# JasminUSBASP.net
KiCad netlist of a schematic drawn in EAGLE
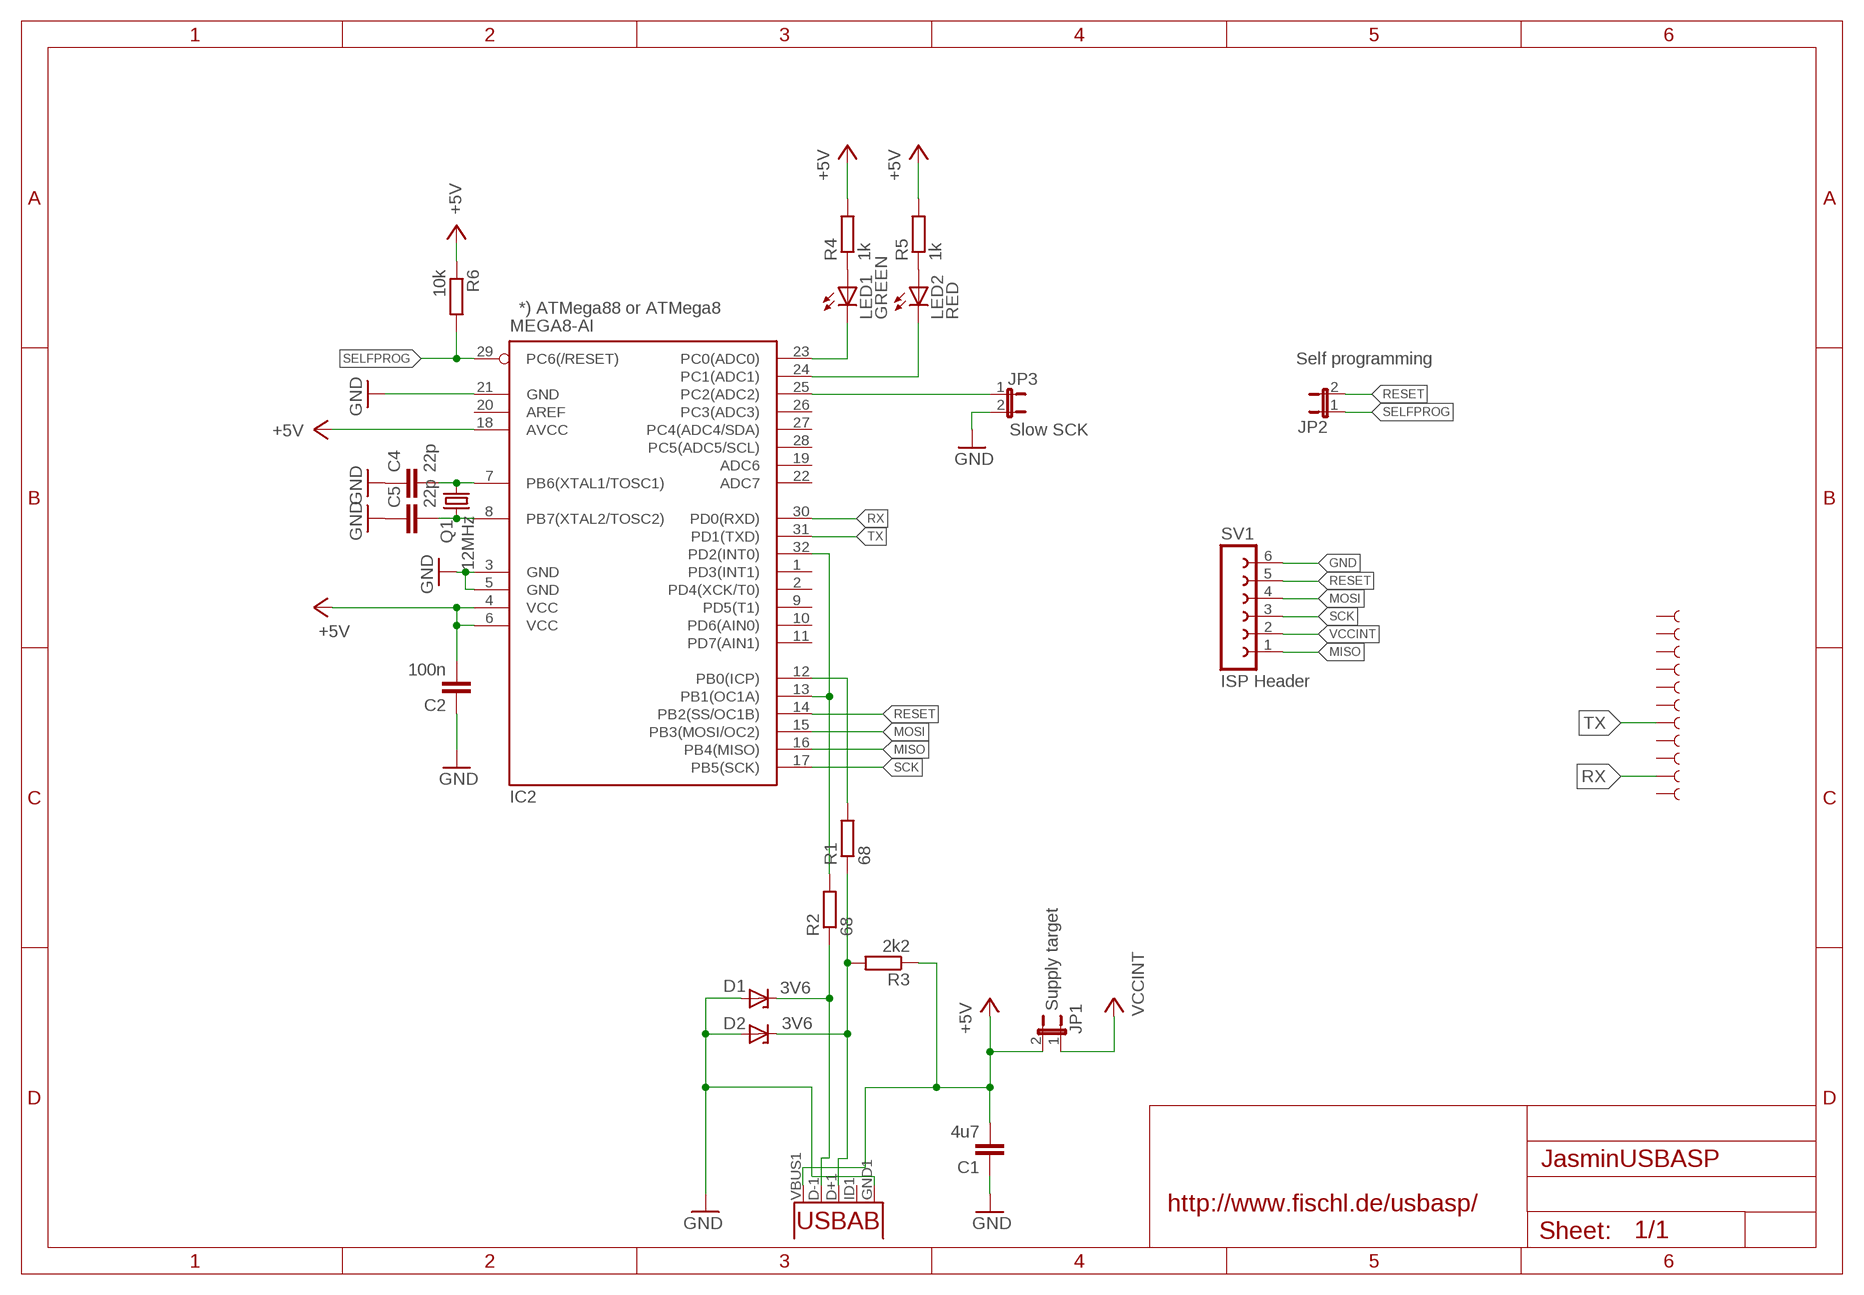
[diagram p0: schematic, sheet 1]

(export (version "E")
  (design (tool "Eeschema 10.0.6"))
  (components
    (comp (ref "A2/16")
      (value "SEWTAP9")
      (footprint "eagle-import:PETAL-LONG-1-2SIDE")
      (libsource (lib "eagle-import") (part "SEWTAP9"))
    )
    (comp (ref "A3/17")
      (value "SEWTAP9")
      (footprint "eagle-import:PETAL-LONG-1-2SIDE")
      (libsource (lib "eagle-import") (part "SEWTAP9"))
    )
    (comp (ref "A4/18")
      (value "SEWTAP9")
      (footprint "eagle-import:PETAL-LONG-1-2SIDE")
      (libsource (lib "eagle-import") (part "SEWTAP9"))
    )
    (comp (ref "A5/19")
      (value "SEWTAP9")
      (footprint "eagle-import:PETAL-LONG-1-2SIDE")
      (libsource (lib "eagle-import") (part "SEWTAP9"))
    )
    (comp (ref "C1")
      (value "4u7")
      (footprint "eagle-import:C1206")
      (libsource (lib "eagle-import") (part "C-EUC1206"))
    )
    (comp (ref "C2")
      (value "100n")
      (footprint "eagle-import:C1206")
      (libsource (lib "eagle-import") (part "C-EUC1206"))
    )
    (comp (ref "C4")
      (value "22p")
      (footprint "eagle-import:C1206")
      (libsource (lib "eagle-import") (part "C-EUC1206"))
    )
    (comp (ref "C5")
      (value "22p")
      (footprint "eagle-import:C1206")
      (libsource (lib "eagle-import") (part "C-EUC1206"))
    )
    (comp (ref "D1")
      (value "3V6")
      (footprint "eagle-import:DO34Z7")
      (libsource (lib "eagle-import") (part "ZENER-DIODEDO34-7"))
    )
    (comp (ref "D2")
      (value "3V6")
      (footprint "eagle-import:DO34Z7")
      (libsource (lib "eagle-import") (part "ZENER-DIODEDO34-7"))
    )
    (comp (ref "IC2")
      (value "MEGA8-AI")
      (footprint "eagle-import:TQFP32-08")
      (fields (field (name "MPN") "ATMEGA8-16AU"))
      (libsource (lib "eagle-import") (part "MEGA8-AI"))
    )
    (comp (ref "JP1")
      (value "Supply target")
      (footprint "eagle-import:JP1")
      (libsource (lib "eagle-import") (part "JP1E"))
    )
    (comp (ref "JP2")
      (value "Self programming")
      (footprint "eagle-import:JP1")
      (libsource (lib "eagle-import") (part "JP1E"))
    )
    (comp (ref "JP3")
      (value "Slow SCK")
      (footprint "eagle-import:JP1")
      (libsource (lib "eagle-import") (part "JP1E"))
    )
    (comp (ref "JP9")
      (value "Micro USB")
      (footprint "eagle-import:USB-AB-MICRO-SMD_V03")
      (libsource (lib "eagle-import") (part "USB-ABCONN-11794"))
    )
    (comp (ref "LED1")
      (value "GREEN")
      (footprint "eagle-import:CHIPLED_1206")
      (libsource (lib "eagle-import") (part "LEDCHIPLED_1206"))
    )
    (comp (ref "LED2")
      (value "RED")
      (footprint "eagle-import:CHIPLED_1206")
      (libsource (lib "eagle-import") (part "LEDCHIPLED_1206"))
    )
    (comp (ref "Q1")
      (value "12MHz")
      (footprint "eagle-import:HC49_S")
      (libsource (lib "eagle-import") (part "CRYTALHC49S"))
    )
    (comp (ref "R1")
      (value "68")
      (footprint "eagle-import:R1206")
      (libsource (lib "eagle-import") (part "R-EU_R1206"))
    )
    (comp (ref "R2")
      (value "68")
      (footprint "eagle-import:R1206")
      (libsource (lib "eagle-import") (part "R-EU_R1206"))
    )
    (comp (ref "R3")
      (value "2k2")
      (footprint "eagle-import:R1206")
      (libsource (lib "eagle-import") (part "R-EU_R1206"))
    )
    (comp (ref "R4")
      (value "1k")
      (footprint "eagle-import:R1206")
      (libsource (lib "eagle-import") (part "R-EU_R1206"))
    )
    (comp (ref "R5")
      (value "1k")
      (footprint "eagle-import:R1206")
      (libsource (lib "eagle-import") (part "R-EU_R1206"))
    )
    (comp (ref "R6")
      (value "10k")
      (footprint "eagle-import:R1206")
      (libsource (lib "eagle-import") (part "R-EU_R1206"))
    )
    (comp (ref "SV1")
      (value "ISP Header")
      (footprint "eagle-import:FE06W")
      (libsource (lib "eagle-import") (part "FE06W"))
    )
    (comp (ref "U$4")
      (value "SEWTAP9")
      (footprint "eagle-import:PETAL-LONG-1-2SIDE")
      (libsource (lib "eagle-import") (part "SEWTAP9"))
    )
    (comp (ref "U$35")
      (value "SEWTAP9")
      (footprint "eagle-import:PETAL-LONG-1-2SIDE")
      (libsource (lib "eagle-import") (part "SEWTAP9"))
    )
    (comp (ref "U$37")
      (value "SEWTAP9")
      (footprint "eagle-import:PETAL-LONG-1-2SIDE")
      (libsource (lib "eagle-import") (part "SEWTAP9"))
    )
    (comp (ref "U$39")
      (value "SEWTAP9")
      (footprint "eagle-import:PETAL-LONG-1-2SIDE")
      (libsource (lib "eagle-import") (part "SEWTAP9"))
    )
    (comp (ref "U$41")
      (value "SEWTAP9")
      (footprint "eagle-import:PETAL-LONG-1-2SIDE")
      (libsource (lib "eagle-import") (part "SEWTAP9"))
    )
    (comp (ref "U$43")
      (value "SEWTAP9")
      (footprint "eagle-import:PETAL-LONG-1-2SIDE")
      (libsource (lib "eagle-import") (part "SEWTAP9"))
    )
    (comp (ref "U$45")
      (value "SEWTAP9")
      (footprint "eagle-import:PETAL-LONG-1-2SIDE")
      (libsource (lib "eagle-import") (part "SEWTAP9"))
    )
  )
  (nets
    (net (code "1") (name "+5V") (class "Default")
      (node (ref "C1") (pin "2") (pinfunction "2_2") (pintype "passive"))
      (node (ref "C2") (pin "2") (pinfunction "2_2") (pintype "passive"))
      (node (ref "IC2") (pin "18") (pinfunction "AVCC_18") (pintype "power_in"))
      (node (ref "IC2") (pin "4") (pinfunction "VCC_4") (pintype "power_in"))
      (node (ref "IC2") (pin "6") (pinfunction "VCC_6") (pintype "power_in"))
      (node (ref "JP1") (pin "2") (pinfunction "2_2") (pintype "passive"))
      (node (ref "JP9") (pin "VBUS1") (pinfunction "VBUS_VBUS1") (pintype "bidirectional"))
      (node (ref "R3") (pin "1") (pinfunction "1_1") (pintype "passive"))
      (node (ref "R4") (pin "2") (pinfunction "2_2") (pintype "passive"))
      (node (ref "R5") (pin "2") (pinfunction "2_2") (pintype "passive"))
      (node (ref "R6") (pin "1") (pinfunction "1_1") (pintype "passive"))
    )
    (net (code "2") (name "GND") (class "Default")
      (node (ref "C1") (pin "1") (pinfunction "1_1") (pintype "passive"))
      (node (ref "C2") (pin "1") (pinfunction "1_1") (pintype "passive"))
      (node (ref "C4") (pin "1") (pinfunction "1_1") (pintype "passive"))
      (node (ref "C5") (pin "1") (pinfunction "1_1") (pintype "passive"))
      (node (ref "D1") (pin "A") (pinfunction "A_A") (pintype "passive"))
      (node (ref "D2") (pin "A") (pinfunction "A_A") (pintype "passive"))
      (node (ref "IC2") (pin "21") (pinfunction "GND_21") (pintype "power_in"))
      (node (ref "IC2") (pin "3") (pinfunction "GND_3") (pintype "power_in"))
      (node (ref "IC2") (pin "5") (pinfunction "GND_5") (pintype "power_in"))
      (node (ref "JP3") (pin "2") (pinfunction "2_2") (pintype "passive"))
      (node (ref "JP9") (pin "GND1") (pinfunction "GND_GND1") (pintype "bidirectional"))
      (node (ref "SV1") (pin "6") (pinfunction "6_6") (pintype "passive"))
    )
    (net (code "3") (name "MISO") (class "Default")
      (node (ref "IC2") (pin "16") (pinfunction "PB4(MISO)_16") (pintype "bidirectional"))
      (node (ref "SV1") (pin "1") (pinfunction "1_1") (pintype "passive"))
    )
    (net (code "4") (name "MOSI") (class "Default")
      (node (ref "IC2") (pin "15") (pinfunction "PB3(MOSI/OC2)_15") (pintype "bidirectional"))
      (node (ref "SV1") (pin "4") (pinfunction "4_4") (pintype "passive"))
    )
    (net (code "5") (name "Net-(IC2-PB0(ICP))") (class "Default")
      (node (ref "IC2") (pin "12") (pinfunction "PB0(ICP)_12") (pintype "bidirectional"))
      (node (ref "R1") (pin "2") (pinfunction "2_2") (pintype "passive"))
    )
    (net (code "6") (name "Net-(IC2-PB1(OC1A))") (class "Default")
      (node (ref "IC2") (pin "13") (pinfunction "PB1(OC1A)_13") (pintype "bidirectional"))
      (node (ref "IC2") (pin "32") (pinfunction "PD2(INT0)_32") (pintype "bidirectional"))
      (node (ref "R2") (pin "2") (pinfunction "2_2") (pintype "passive"))
    )
    (net (code "7") (name "Net-(IC2-PB6(XTAL1{slash}TOSC1))") (class "Default")
      (node (ref "C4") (pin "2") (pinfunction "2_2") (pintype "passive"))
      (node (ref "IC2") (pin "7") (pinfunction "PB6(XTAL1/TOSC1)_7") (pintype "bidirectional"))
      (node (ref "Q1") (pin "2") (pinfunction "2_2") (pintype "passive"))
    )
    (net (code "8") (name "Net-(IC2-PB7(XTAL2{slash}TOSC2))") (class "Default")
      (node (ref "C5") (pin "2") (pinfunction "2_2") (pintype "passive"))
      (node (ref "IC2") (pin "8") (pinfunction "PB7(XTAL2/TOSC2)_8") (pintype "bidirectional"))
      (node (ref "Q1") (pin "1") (pinfunction "1_1") (pintype "passive"))
    )
    (net (code "9") (name "Net-(IC2-PC0(ADC0))") (class "Default")
      (node (ref "IC2") (pin "23") (pinfunction "PC0(ADC0)_23") (pintype "bidirectional"))
      (node (ref "LED1") (pin "C") (pinfunction "C_C") (pintype "passive"))
    )
    (net (code "10") (name "Net-(IC2-PC1(ADC1))") (class "Default")
      (node (ref "IC2") (pin "24") (pinfunction "PC1(ADC1)_24") (pintype "bidirectional"))
      (node (ref "LED2") (pin "C") (pinfunction "C_C") (pintype "passive"))
    )
    (net (code "11") (name "Net-(IC2-PC2(ADC2))") (class "Default")
      (node (ref "IC2") (pin "25") (pinfunction "PC2(ADC2)_25") (pintype "bidirectional"))
      (node (ref "JP3") (pin "1") (pinfunction "1_1") (pintype "passive"))
    )
    (net (code "12") (name "Net-(JP9-D+)") (class "Default")
      (node (ref "D2") (pin "C") (pinfunction "C_C") (pintype "passive"))
      (node (ref "JP9") (pin "D+1") (pinfunction "D+_D+1") (pintype "bidirectional"))
      (node (ref "R1") (pin "1") (pinfunction "1_1") (pintype "passive"))
      (node (ref "R3") (pin "2") (pinfunction "2_2") (pintype "passive"))
    )
    (net (code "13") (name "Net-(JP9-D-)") (class "Default")
      (node (ref "D1") (pin "C") (pinfunction "C_C") (pintype "passive"))
      (node (ref "JP9") (pin "D-1") (pinfunction "D-_D-1") (pintype "bidirectional"))
      (node (ref "R2") (pin "1") (pinfunction "1_1") (pintype "passive"))
    )
    (net (code "14") (name "Net-(LED1-PadA)") (class "Default")
      (node (ref "LED1") (pin "A") (pinfunction "A_A") (pintype "passive"))
      (node (ref "R4") (pin "1") (pinfunction "1_1") (pintype "passive"))
    )
    (net (code "15") (name "Net-(LED2-PadA)") (class "Default")
      (node (ref "LED2") (pin "A") (pinfunction "A_A") (pintype "passive"))
      (node (ref "R5") (pin "1") (pinfunction "1_1") (pintype "passive"))
    )
    (net (code "16") (name "RESET") (class "Default")
      (node (ref "IC2") (pin "14") (pinfunction "PB2(SS/OC1B)_14") (pintype "bidirectional"))
      (node (ref "JP2") (pin "2") (pinfunction "2_2") (pintype "passive"))
      (node (ref "SV1") (pin "5") (pinfunction "5_5") (pintype "passive"))
    )
    (net (code "17") (name "RX") (class "Default")
      (node (ref "IC2") (pin "30") (pinfunction "PD0(RXD)_30") (pintype "bidirectional"))
      (node (ref "U$39") (pin "1") (pinfunction "1_1") (pintype "bidirectional"))
    )
    (net (code "18") (name "SCK") (class "Default")
      (node (ref "IC2") (pin "17") (pinfunction "PB5(SCK)_17") (pintype "bidirectional"))
      (node (ref "SV1") (pin "3") (pinfunction "3_3") (pintype "passive"))
    )
    (net (code "19") (name "SELFPROG") (class "Default")
      (node (ref "IC2") (pin "29") (pinfunction "PC6(/RESET)_29") (pintype "bidirectional"))
      (node (ref "JP2") (pin "1") (pinfunction "1_1") (pintype "passive"))
      (node (ref "R6") (pin "2") (pinfunction "2_2") (pintype "passive"))
    )
    (net (code "20") (name "TX") (class "Default")
      (node (ref "IC2") (pin "31") (pinfunction "PD1(TXD)_31") (pintype "bidirectional"))
      (node (ref "U$41") (pin "1") (pinfunction "1_1") (pintype "bidirectional"))
    )
    (net (code "21") (name "VCCINT") (class "Default")
      (node (ref "JP1") (pin "1") (pinfunction "1_1") (pintype "passive"))
      (node (ref "SV1") (pin "2") (pinfunction "2_2") (pintype "passive"))
    )
    (net (code "22") (name "unconnected-(A2/16-Pad1)") (class "Default")
      (node (ref "A2/16") (pin "1") (pinfunction "1_1") (pintype "bidirectional"))
    )
    (net (code "23") (name "unconnected-(A3/17-Pad1)") (class "Default")
      (node (ref "A3/17") (pin "1") (pinfunction "1_1") (pintype "bidirectional"))
    )
    (net (code "24") (name "unconnected-(A4/18-Pad1)") (class "Default")
      (node (ref "A4/18") (pin "1") (pinfunction "1_1") (pintype "bidirectional"))
    )
    (net (code "25") (name "unconnected-(A5/19-Pad1)") (class "Default")
      (node (ref "A5/19") (pin "1") (pinfunction "1_1") (pintype "bidirectional"))
    )
    (net (code "26") (name "unconnected-(IC2-ADC6-Pad19)") (class "Default")
      (node (ref "IC2") (pin "19") (pinfunction "ADC6_19") (pintype "bidirectional"))
    )
    (net (code "27") (name "unconnected-(IC2-ADC7-Pad22)") (class "Default")
      (node (ref "IC2") (pin "22") (pinfunction "ADC7_22") (pintype "bidirectional"))
    )
    (net (code "28") (name "unconnected-(IC2-AREF-Pad20)") (class "Default")
      (node (ref "IC2") (pin "20") (pinfunction "AREF_20") (pintype "passive"))
    )
    (net (code "29") (name "unconnected-(IC2-PC3(ADC3)-Pad26)") (class "Default")
      (node (ref "IC2") (pin "26") (pinfunction "PC3(ADC3)_26") (pintype "bidirectional"))
    )
    (net (code "30") (name "unconnected-(IC2-PC4(ADC4{slash}SDA)-Pad27)") (class "Default")
      (node (ref "IC2") (pin "27") (pinfunction "PC4(ADC4/SDA)_27") (pintype "bidirectional"))
    )
    (net (code "31") (name "unconnected-(IC2-PC5(ADC5{slash}SCL)-Pad28)") (class "Default")
      (node (ref "IC2") (pin "28") (pinfunction "PC5(ADC5/SCL)_28") (pintype "bidirectional"))
    )
    (net (code "32") (name "unconnected-(IC2-PD3(INT1)-Pad1)") (class "Default")
      (node (ref "IC2") (pin "1") (pinfunction "PD3(INT1)_1") (pintype "bidirectional"))
    )
    (net (code "33") (name "unconnected-(IC2-PD4(XCK{slash}T0)-Pad2)") (class "Default")
      (node (ref "IC2") (pin "2") (pinfunction "PD4(XCK/T0)_2") (pintype "bidirectional"))
    )
    (net (code "34") (name "unconnected-(IC2-PD5(T1)-Pad9)") (class "Default")
      (node (ref "IC2") (pin "9") (pinfunction "PD5(T1)_9") (pintype "bidirectional"))
    )
    (net (code "35") (name "unconnected-(IC2-PD6(AIN0)-Pad10)") (class "Default")
      (node (ref "IC2") (pin "10") (pinfunction "PD6(AIN0)_10") (pintype "bidirectional"))
    )
    (net (code "36") (name "unconnected-(IC2-PD7(AIN1)-Pad11)") (class "Default")
      (node (ref "IC2") (pin "11") (pinfunction "PD7(AIN1)_11") (pintype "bidirectional"))
    )
    (net (code "37") (name "unconnected-(JP9-USBID-PadID1)") (class "Default")
      (node (ref "JP9") (pin "ID1") (pinfunction "USBID_ID1") (pintype "bidirectional"))
    )
    (net (code "38") (name "unconnected-(U$4-Pad1)") (class "Default")
      (node (ref "U$4") (pin "1") (pinfunction "1_1") (pintype "bidirectional"))
    )
    (net (code "39") (name "unconnected-(U$35-Pad1)") (class "Default")
      (node (ref "U$35") (pin "1") (pinfunction "1_1") (pintype "bidirectional"))
    )
    (net (code "40") (name "unconnected-(U$37-Pad1)") (class "Default")
      (node (ref "U$37") (pin "1") (pinfunction "1_1") (pintype "bidirectional"))
    )
    (net (code "41") (name "unconnected-(U$43-Pad1)") (class "Default")
      (node (ref "U$43") (pin "1") (pinfunction "1_1") (pintype "bidirectional"))
    )
    (net (code "42") (name "unconnected-(U$45-Pad1)") (class "Default")
      (node (ref "U$45") (pin "1") (pinfunction "1_1") (pintype "bidirectional"))
    )
  )
)
